# UAVCAN_LIDAR.net
KiCad netlist of a schematic drawn in Altium Designer
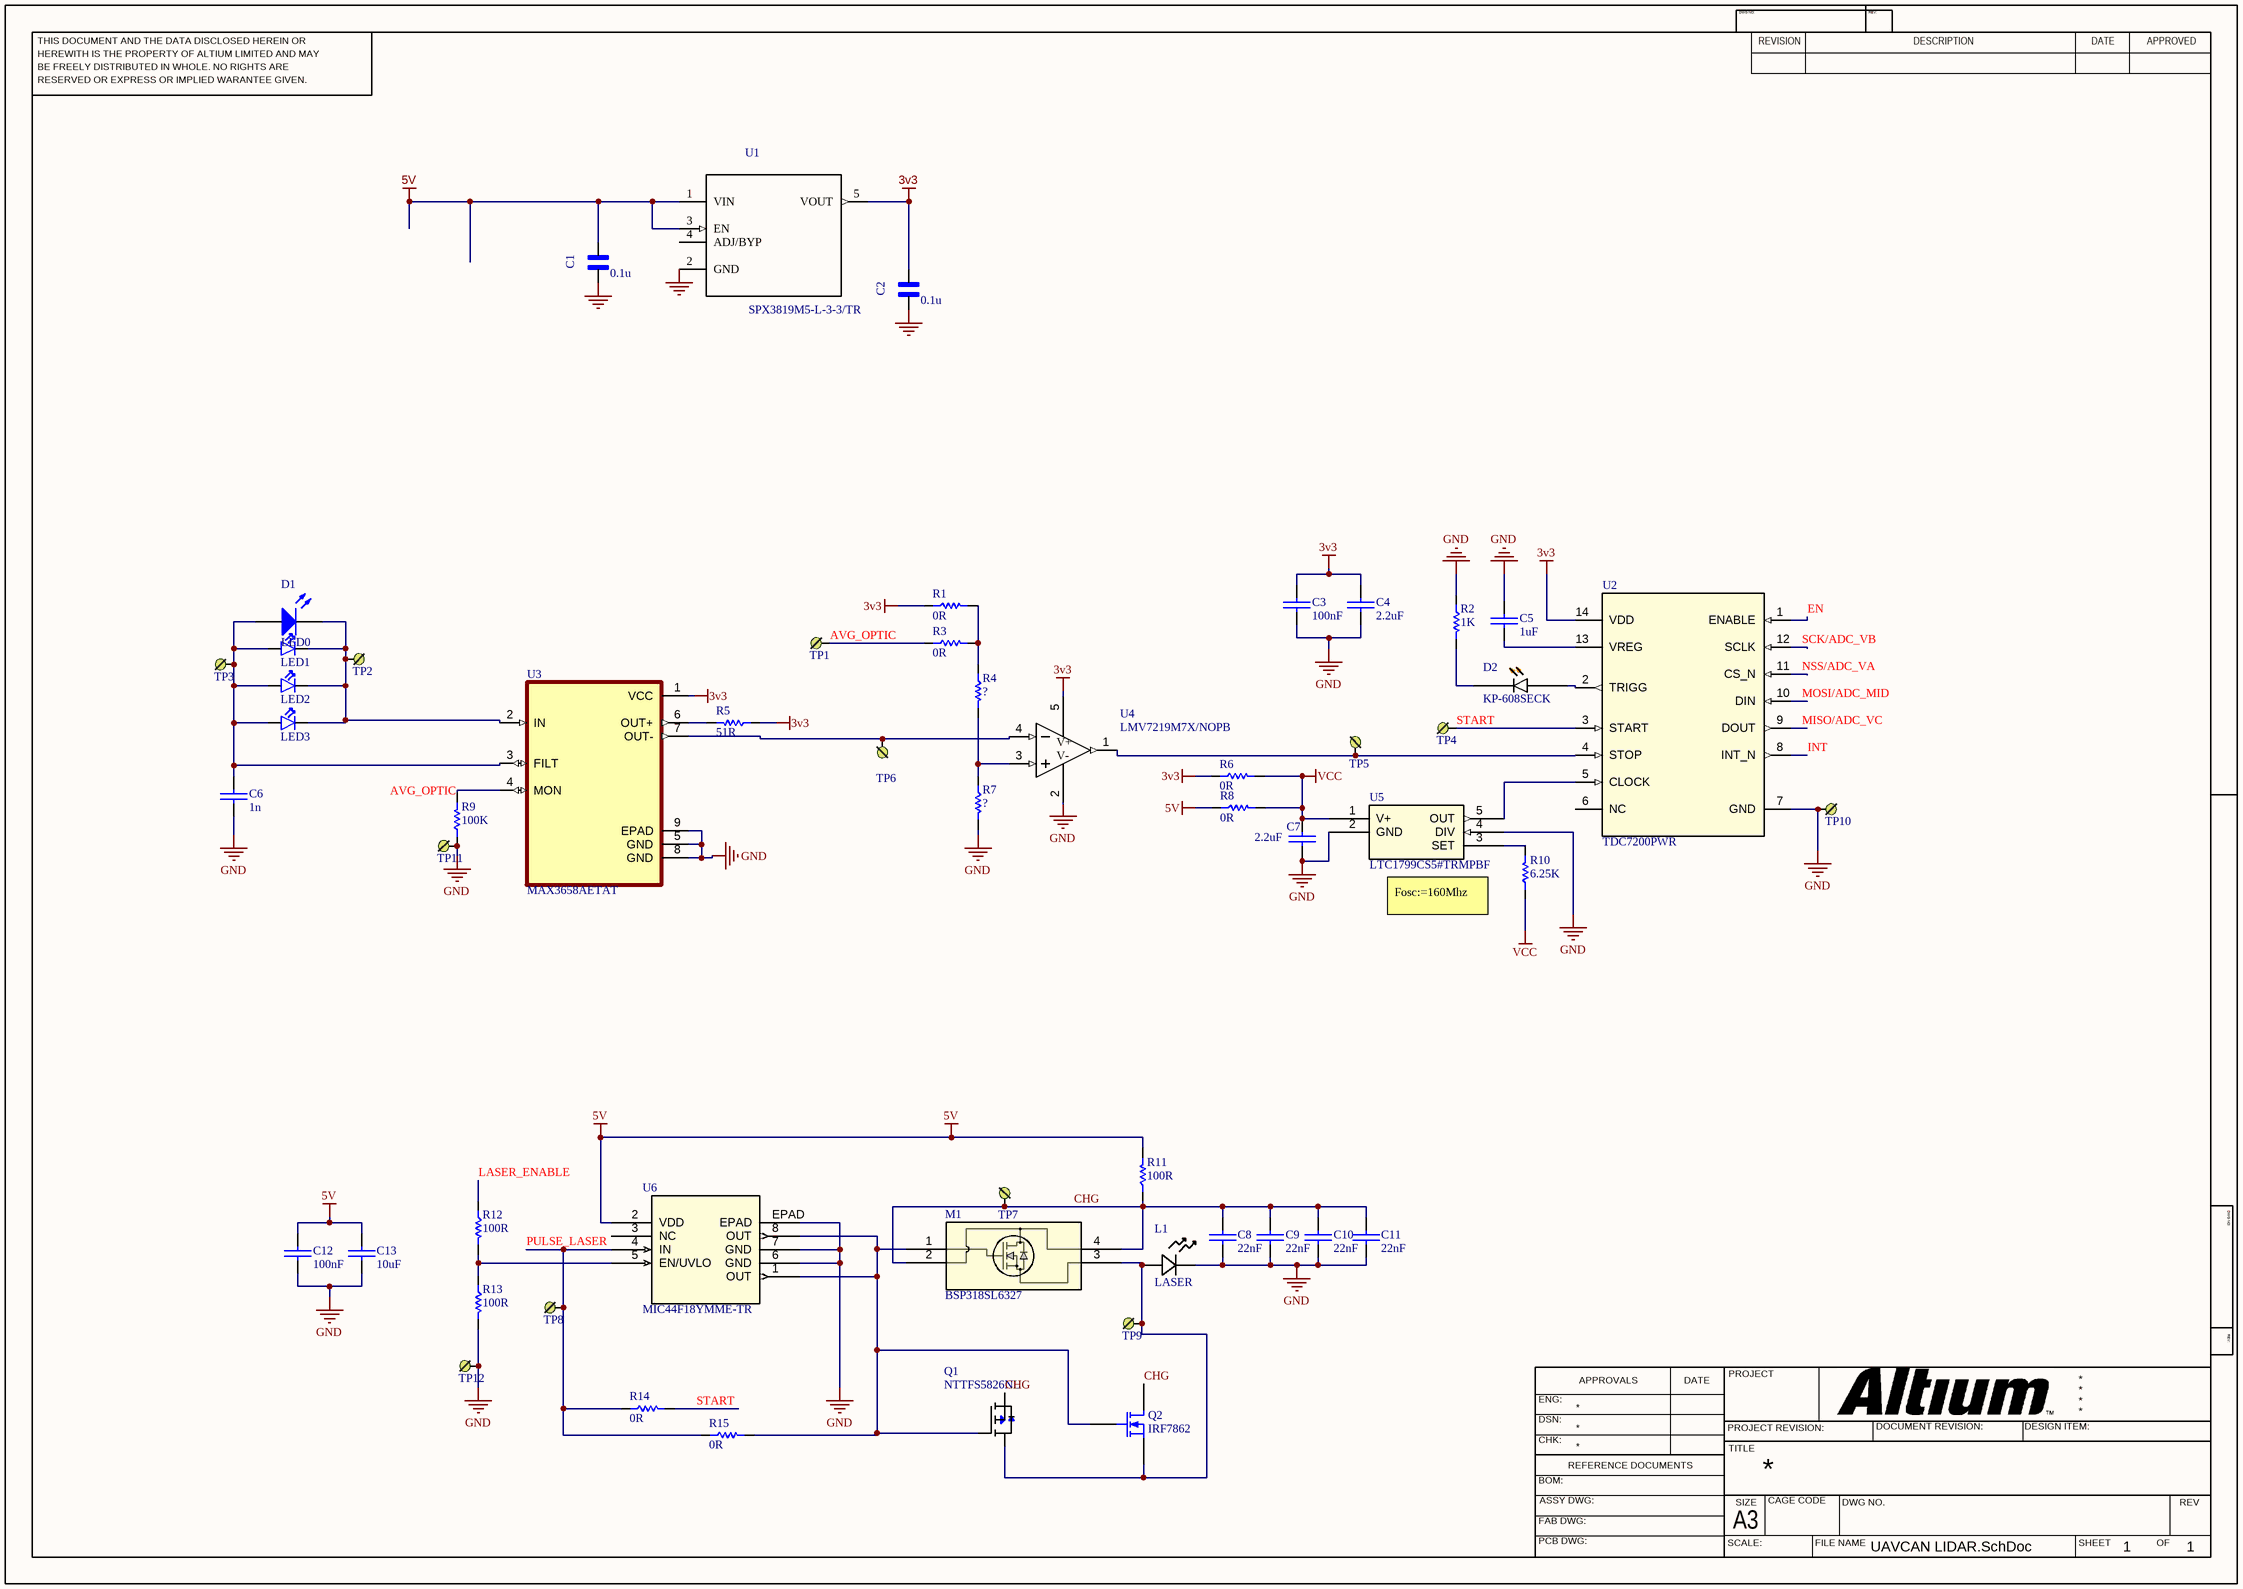
[diagram p0: UAVCAN LIDAR.SchDoc]

(export (version "E")
  (design (tool "Eeschema 10.0.6"))
  (components
    (comp (ref "C1")
      (value "0.1u")
      (footprint "*CAPC1608X90")
      (description "Cap Thin Film 0.1uf 50v 0603")
      (fields (field (name "MF") "AVX") (field (name "MP") "GX035C104MAT2-500"))
      (libsource (lib "lib") (part "GX035C104MAT2-500"))
    )
    (comp (ref "C2")
      (value "0.1u")
      (footprint "*CAPC1608X90")
      (description "Cap Thin Film 0.1uf 50v 0603")
      (fields (field (name "MF") "AVX") (field (name "MP") "GX035C104MAT2-500"))
      (libsource (lib "lib") (part "GX035C104MAT2-500"))
    )
    (comp (ref "C3")
      (value "100nF")
      (footprint "SMD_CAP_0603")
      (description "Bipolar Capacitor")
      (fields (field (name "VOLTAGE") "100V") (field (name "DESIGNER") "Saeid Jorablo"))
      (libsource (lib "R2T Team Library") (part "Cap-Bipolar"))
    )
    (comp (ref "C4")
      (value "2.2uF")
      (footprint "SMD_CAP_0603")
      (description "Bipolar Capacitor")
      (fields (field (name "VOLTAGE") "100V") (field (name "DESIGNER") "Saeid Jorablo"))
      (libsource (lib "R2T Team Library") (part "Cap-Bipolar"))
    )
    (comp (ref "C5")
      (value "1uF")
      (footprint "SMD_CAP_0603")
      (description "Bipolar Capacitor")
      (fields (field (name "VOLTAGE") "100V") (field (name "DESIGNER") "Saeid Jorablo"))
      (libsource (lib "R2T Team Library") (part "Cap-Bipolar"))
    )
    (comp (ref "C6")
      (value "1n")
      (footprint "SMD_CAP_0603")
      (description "Bipolar Capacitor")
      (fields (field (name "VOLTAGE") "100V") (field (name "DESIGNER") "Saeid Jorablo"))
      (libsource (lib "R2T Team Library") (part "Cap-Bipolar"))
    )
    (comp (ref "C7")
      (value "2.2uF")
      (footprint "SMD_CAP_0603")
      (description "Bipolar Capacitor")
      (fields (field (name "VOLTAGE") "100V") (field (name "DESIGNER") "Saeid Jorablo"))
      (libsource (lib "R2T Team Library") (part "Cap-Bipolar"))
    )
    (comp (ref "C8")
      (value "22nF")
      (footprint "SMD_CAP_0603")
      (description "Bipolar Capacitor")
      (fields (field (name "VOLTAGE") "100V") (field (name "DESIGNER") "Saeid Jorablo"))
      (libsource (lib "R2T Team Library") (part "Cap-Bipolar"))
    )
    (comp (ref "C9")
      (value "22nF")
      (footprint "SMD_CAP_0603")
      (description "Bipolar Capacitor")
      (fields (field (name "VOLTAGE") "100V") (field (name "DESIGNER") "Saeid Jorablo"))
      (libsource (lib "R2T Team Library") (part "Cap-Bipolar"))
    )
    (comp (ref "C10")
      (value "22nF")
      (footprint "SMD_CAP_0603")
      (description "Bipolar Capacitor")
      (fields (field (name "VOLTAGE") "100V") (field (name "DESIGNER") "Saeid Jorablo"))
      (libsource (lib "R2T Team Library") (part "Cap-Bipolar"))
    )
    (comp (ref "C11")
      (value "22nF")
      (footprint "SMD_CAP_0603")
      (description "Bipolar Capacitor")
      (fields (field (name "VOLTAGE") "100V") (field (name "DESIGNER") "Saeid Jorablo"))
      (libsource (lib "R2T Team Library") (part "Cap-Bipolar"))
    )
    (comp (ref "C12")
      (value "100nF")
      (footprint "SMD_CAP_0603")
      (description "Bipolar Capacitor")
      (fields (field (name "VOLTAGE") "100V") (field (name "DESIGNER") "Saeid Jorablo"))
      (libsource (lib "R2T Team Library") (part "Cap-Bipolar"))
    )
    (comp (ref "C13")
      (value "10uF")
      (footprint "SMD_CAP_0603")
      (description "Bipolar Capacitor")
      (fields (field (name "VOLTAGE") "100V") (field (name "DESIGNER") "Saeid Jorablo"))
      (libsource (lib "R2T Team Library") (part "Cap-Bipolar"))
    )
    (comp (ref "D1")
      (value "LED0")
      (footprint "LED-0")
      (description "Typical INFRARED GaAs LED")
      (fields (field (name "PUBLISHER") "Altium Limited"))
      (libsource (lib "Miscellaneous Devices") (part "LED0"))
    )
    (comp (ref "D2")
      (value "KP-608SECK")
      (footprint "*LEDM1608X80_LTE-C1906R-14(Primary)")
      (description "Orange 605nm LED Indication - Discrete 2.2V 0603 (1608 Metric)")
      (fields (field (name "MP") "SML-D12D1WT86 or LTST-C194KFKT"))
      (libsource (lib "lib") (part "0603-LED-ORANGE"))
    )
    (comp (ref "L1")
      (value "LASER")
      (footprint "SPL-PL90")
      (description "5mm Laser beam transmitter")
      (fields (field (name "DESIGNER") "EhsanShaghaei"))
      (libsource (lib "lib") (part "SPL-PL90"))
    )
    (comp (ref "LED1")
      (value "LED")
      (footprint "LED1206")
      (fields (field (name "DESIGNER :") "Razi Research Team Of Mashhad - Hamed Jafarzadeh"))
      (libsource (lib "R2T Team Library") (part "LED"))
    )
    (comp (ref "LED2")
      (value "LED")
      (footprint "LED0805")
      (fields (field (name "DESIGNER :") "Razi Research Team Of Mashhad - Hamed Jafarzadeh"))
      (libsource (lib "R2T Team Library") (part "LED"))
    )
    (comp (ref "LED3")
      (value "LED")
      (footprint "LED0603")
      (fields (field (name "DESIGNER :") "Razi Research Team Of Mashhad - Hamed Jafarzadeh"))
      (libsource (lib "R2T Team Library") (part "LED"))
    )
    (comp (ref "M1")
      (value "BSP318SL6327")
      (footprint "PG-SOT223-4_INF-L")
      (description "No Description Available")
      (fields
        (field (name "COPYRIGHT") "Copyright (C) 2018 Accelerated Designs. All rights reserved")
        (field (name "DESIGNER") "EhsanShaghaei")
      )
      (libsource (lib "lib") (part "BSP318SL6327"))
    )
    (comp (ref "Q1")
      (value "NTTFS5826NL")
      (footprint "*TRANS_NVTFS015N04CTAG")
      (description "NTTFS5826NLTAG, MOSFET N-CHANNEL 60V 20A 24MOHM WDFN8")
      (libsource (lib "lib") (part "NTTFS5826NL"))
    )
    (comp (ref "Q2")
      (value "IRF7862")
      (footprint "*SO-08")
      (description "N-Channel MOSFET")
      (fields (field (name "PUBLISHER") "Altium Limited"))
      (libsource (lib "lib") (part "IRF7862"))
    )
    (comp (ref "R1")
      (value "0R")
      (footprint "RES 0603 (1608X06L)")
      (description "Resistor")
      (fields (field (name "TOLERANCE") "5%") (field (name "POWER") "1/8 W"))
      (libsource (lib "R2T Team Library") (part "Resistor"))
    )
    (comp (ref "R2")
      (value "1K")
      (footprint "RES 0603 (1608X06L)")
      (description "Resistor")
      (fields (field (name "TOLERANCE") "5%") (field (name "POWER") "1/8 W"))
      (libsource (lib "R2T Team Library") (part "Resistor"))
    )
    (comp (ref "R3")
      (value "0R")
      (footprint "RES 0603 (1608X06L)")
      (description "Resistor")
      (fields (field (name "TOLERANCE") "5%") (field (name "POWER") "1/8 W"))
      (libsource (lib "R2T Team Library") (part "Resistor"))
    )
    (comp (ref "R4")
      (value "?")
      (footprint "RES 0603 (1608X06L)")
      (description "Resistor")
      (fields (field (name "TOLERANCE") "5%") (field (name "POWER") "1/8 W"))
      (libsource (lib "R2T Team Library") (part "Resistor"))
    )
    (comp (ref "R5")
      (value "51R")
      (footprint "RES 0603 (1608X06L)")
      (description "Resistor")
      (fields (field (name "TOLERANCE") "5%") (field (name "POWER") "1/8 W"))
      (libsource (lib "R2T Team Library") (part "Resistor"))
    )
    (comp (ref "R6")
      (value "0R")
      (footprint "RES 0603 (1608X06L)")
      (description "Resistor")
      (fields (field (name "TOLERANCE") "5%") (field (name "POWER") "1/8 W"))
      (libsource (lib "R2T Team Library") (part "Resistor"))
    )
    (comp (ref "R7")
      (value "?")
      (footprint "RES 0603 (1608X06L)")
      (description "Resistor")
      (fields (field (name "TOLERANCE") "5%") (field (name "POWER") "1/8 W"))
      (libsource (lib "R2T Team Library") (part "Resistor"))
    )
    (comp (ref "R8")
      (value "0R")
      (footprint "RES 0603 (1608X06L)")
      (description "Resistor")
      (fields (field (name "TOLERANCE") "5%") (field (name "POWER") "1/8 W"))
      (libsource (lib "R2T Team Library") (part "Resistor"))
    )
    (comp (ref "R9")
      (value "100K")
      (footprint "RES 0603 (1608X06L)")
      (description "Resistor")
      (fields (field (name "TOLERANCE") "5%") (field (name "POWER") "1/8 W"))
      (libsource (lib "R2T Team Library") (part "Resistor"))
    )
    (comp (ref "R10")
      (value "6.25K")
      (footprint "RES 0603 (1608X06L)")
      (description "Resistor")
      (fields (field (name "TOLERANCE") "5%") (field (name "POWER") "1/8 W"))
      (libsource (lib "R2T Team Library") (part "Resistor"))
    )
    (comp (ref "R11")
      (value "100R")
      (footprint "RES 1210 (3226X07L)")
      (description "Resistor")
      (fields (field (name "TOLERANCE") "5%") (field (name "POWER") "1/8 W"))
      (libsource (lib "R2T Team Library") (part "Resistor"))
    )
    (comp (ref "R12")
      (value "100R")
      (footprint "RES 0603 (1608X06L)")
      (description "Resistor")
      (fields (field (name "TOLERANCE") "5%") (field (name "POWER") "1/8 W"))
      (libsource (lib "R2T Team Library") (part "Resistor"))
    )
    (comp (ref "R13")
      (value "100R")
      (footprint "RES 0603 (1608X06L)")
      (description "Resistor")
      (fields (field (name "TOLERANCE") "5%") (field (name "POWER") "1/8 W"))
      (libsource (lib "R2T Team Library") (part "Resistor"))
    )
    (comp (ref "R14")
      (value "0R")
      (footprint "RES 0603 (1608X06L)")
      (description "Resistor")
      (fields (field (name "TOLERANCE") "5%") (field (name "POWER") "1/8 W"))
      (libsource (lib "R2T Team Library") (part "Resistor"))
    )
    (comp (ref "R15")
      (value "0R")
      (footprint "RES 0603 (1608X06L)")
      (description "Resistor")
      (fields (field (name "TOLERANCE") "5%") (field (name "POWER") "1/8 W"))
      (libsource (lib "R2T Team Library") (part "Resistor"))
    )
    (comp (ref "TP1") (value "Test Point") (footprint "PAD1") (libsource (lib "lib") (part "PLUG")))
    (comp (ref "TP2") (value "Test Point") (footprint "PAD1") (libsource (lib "lib") (part "PLUG")))
    (comp (ref "TP3") (value "Test Point") (footprint "PAD1") (libsource (lib "lib") (part "PLUG")))
    (comp (ref "TP4") (value "Test Point") (footprint "PAD1") (libsource (lib "lib") (part "PLUG")))
    (comp (ref "TP5") (value "Test Point") (footprint "PAD1") (libsource (lib "lib") (part "PLUG")))
    (comp (ref "TP6") (value "Test Point") (footprint "PAD1") (libsource (lib "lib") (part "PLUG")))
    (comp (ref "TP7") (value "Test Point") (footprint "PAD1") (libsource (lib "lib") (part "PLUG")))
    (comp (ref "TP8") (value "Test Point") (footprint "PAD1") (libsource (lib "lib") (part "PLUG")))
    (comp (ref "TP9") (value "Test Point") (footprint "PAD1") (libsource (lib "lib") (part "PLUG")))
    (comp (ref "TP10") (value "Test Point") (footprint "PAD1") (libsource (lib "lib") (part "PLUG")))
    (comp (ref "TP11") (value "Test Point") (footprint "PAD1") (libsource (lib "lib") (part "PLUG")))
    (comp (ref "TP12") (value "Test Point") (footprint "PAD1") (libsource (lib "lib") (part "PLUG")))
    (comp (ref "U1")
      (value "SPX3819M5-L-3-3/TR")
      (footprint "*SOT95P280X145-5N")
      (description "Low Dropout Voltage Regulator, Adjustable 0.5A, В±1%, 2.5 to 16 Vin, 5-Pin SOT-23")
      (fields (field (name "MF") "MaxLinear, Inc."))
      (libsource (lib "DC_DC") (part "SPX3819M5-L"))
    )
    (comp (ref "U2")
      (value "TDC7200PWR")
      (footprint "PW0014A_L")
      (fields (field (name "DESIGNER") "Ehsan Shaghaei"))
      (libsource (lib "lib") (part "TDC7200PWR"))
    )
    (comp (ref "U3")
      (value "MAX3658AETAT")
      (footprint "SON65P300X300X80-9N")
      (fields (field (name "MF") "{'manufacturer': u'Maxim Integrated'}"))
      (libsource (lib "SnapEDA_Library") (part "MAX3658AETAT"))
    )
    (comp (ref "U4")
      (value "LMV7219M7X/NOPB")
      (footprint "SOT-5_S_LIT")
      (fields
        (field (name "PARTNUMBER") "LMV7219M7")
        (field (name "MANUFACTURER") "NationalSemiconductor")
        (field (name "COPYRIGHT") "Copyright (C) 2018 Accelerated Designs. All rights reserved")
        (field (name "PUBLISHER") "NationalSemiconductor")
        (field (name "DESIGNER") "EhsanShaghaei")
      )
      (libsource (lib "lib") (part "LMV7219M7X/NOPB"))
    )
    (comp (ref "U5")
      (value "LTC1799CS5#TRMPBF")
      (footprint "SOT-5_S_LIT")
      (fields (field (name "COPYRIGHT") "Copyright (C) 2018 Accelerated Designs. All rights reserved"))
      (libsource (lib "lib") (part "LTC1799CS5"))
    )
    (comp (ref "U6")
      (value "MIC44F18YMME-TR")
      (footprint "SOP65P490X104-9N")
      (description "No Description Available")
      (fields
        (field (name "COPYRIGHT") "Copyright (C) 2018 Accelerated Designs. All rights reserved")
        (field (name "DESIGNER") "Ehsan Shaghaei")
      )
      (libsource (lib "lib") (part "MIC44F18YMME-TR"))
    )
  )
  (nets
    (net (code "1") (name "/AVG_OPTIC") (class "Default")
      (node (ref "R3") (pin "1") (pinfunction "1_1") (pintype "passive"))
      (node (ref "R9") (pin "2") (pinfunction "2_2") (pintype "passive"))
      (node (ref "TP1") (pin "1") (pintype "passive"))
      (node (ref "U3") (pin "4") (pinfunction "MON_4") (pintype "bidirectional"))
    )
    (net (code "2") (name "/CHG") (class "Default")
      (node (ref "C10") (pin "1") (pinfunction "+_1") (pintype "passive"))
      (node (ref "C11") (pin "1") (pinfunction "+_1") (pintype "passive"))
      (node (ref "C8") (pin "1") (pinfunction "+_1") (pintype "passive"))
      (node (ref "C9") (pin "1") (pinfunction "+_1") (pintype "passive"))
      (node (ref "M1") (pin "2") (pinfunction "2_2") (pintype "passive"))
      (node (ref "M1") (pin "4") (pinfunction "4_4") (pintype "passive"))
      (node (ref "Q1") (pin "S") (pinfunction "S_S") (pintype "passive"))
      (node (ref "Q2") (pin "D") (pinfunction "D_D") (pintype "passive"))
      (node (ref "R11") (pin "1") (pinfunction "1_1") (pintype "passive"))
      (node (ref "TP7") (pin "1") (pintype "passive"))
    )
    (net (code "3") (name "/EN") (class "Default")
      (node (ref "U2") (pin "1") (pinfunction "ENABLE_1") (pintype "input"))
    )
    (net (code "4") (name "/INT") (class "Default")
      (node (ref "U2") (pin "8") (pinfunction "INT_N_8") (pintype "output"))
    )
    (net (code "5") (name "/LASER_ENABLE") (class "Default")
      (node (ref "R12") (pin "1") (pinfunction "1_1") (pintype "passive"))
    )
    (net (code "6") (name "/MISO{slash}ADC_VC") (class "Default")
      (node (ref "U2") (pin "9") (pinfunction "DOUT_9") (pintype "output"))
    )
    (net (code "7") (name "/MOSI{slash}ADC_MID") (class "Default")
      (node (ref "U2") (pin "10") (pinfunction "DIN_10") (pintype "input"))
    )
    (net (code "8") (name "/NSS{slash}ADC_VA") (class "Default")
      (node (ref "U2") (pin "11") (pinfunction "CS_N_11") (pintype "input"))
    )
    (net (code "9") (name "/PULSE_LASER") (class "Default")
      (node (ref "R14") (pin "1") (pinfunction "1_1") (pintype "passive"))
      (node (ref "R15") (pin "1") (pinfunction "1_1") (pintype "passive"))
      (node (ref "TP8") (pin "1") (pintype "passive"))
      (node (ref "U6") (pin "4") (pinfunction "IN_4") (pintype "input"))
    )
    (net (code "10") (name "/SCK{slash}ADC_VB") (class "Default")
      (node (ref "U2") (pin "12") (pinfunction "SCLK_12") (pintype "input"))
    )
    (net (code "11") (name "/START") (class "Default")
      (node (ref "R14") (pin "2") (pinfunction "2_2") (pintype "passive"))
      (node (ref "TP4") (pin "1") (pintype "passive"))
      (node (ref "U2") (pin "3") (pinfunction "START_3") (pintype "input"))
    )
    (net (code "12") (name "3v3") (class "Default")
      (node (ref "C2") (pin "1") (pinfunction "1_1") (pintype "passive"))
      (node (ref "C3") (pin "1") (pinfunction "+_1") (pintype "passive"))
      (node (ref "C4") (pin "1") (pinfunction "+_1") (pintype "passive"))
      (node (ref "R1") (pin "1") (pinfunction "1_1") (pintype "passive"))
      (node (ref "R5") (pin "1") (pinfunction "1_1") (pintype "passive"))
      (node (ref "R6") (pin "1") (pinfunction "1_1") (pintype "passive"))
      (node (ref "U1") (pin "5") (pinfunction "VOUT_5") (pintype "output"))
      (node (ref "U2") (pin "14") (pinfunction "VDD_14") (pintype "power_in"))
      (node (ref "U3") (pin "1") (pinfunction "VCC_1") (pintype "power_in"))
      (node (ref "U4") (pin "5") (pinfunction "V+_5") (pintype "power_in"))
    )
    (net (code "13") (name "5V") (class "Default")
      (node (ref "C1") (pin "1") (pinfunction "1_1") (pintype "passive"))
      (node (ref "C12") (pin "1") (pinfunction "+_1") (pintype "passive"))
      (node (ref "C13") (pin "1") (pinfunction "+_1") (pintype "passive"))
      (node (ref "R11") (pin "2") (pinfunction "2_2") (pintype "passive"))
      (node (ref "R8") (pin "1") (pinfunction "1_1") (pintype "passive"))
      (node (ref "U1") (pin "1") (pinfunction "VIN_1") (pintype "power_in"))
      (node (ref "U1") (pin "3") (pinfunction "EN_3") (pintype "input"))
      (node (ref "U6") (pin "2") (pinfunction "VDD_2") (pintype "power_in"))
    )
    (net (code "14") (name "GND") (class "Default")
      (node (ref "C1") (pin "2") (pinfunction "2_2") (pintype "passive"))
      (node (ref "C10") (pin "2") (pinfunction "-_2") (pintype "passive"))
      (node (ref "C11") (pin "2") (pinfunction "-_2") (pintype "passive"))
      (node (ref "C12") (pin "2") (pinfunction "-_2") (pintype "passive"))
      (node (ref "C13") (pin "2") (pinfunction "-_2") (pintype "passive"))
      (node (ref "C2") (pin "2") (pinfunction "2_2") (pintype "passive"))
      (node (ref "C3") (pin "2") (pinfunction "-_2") (pintype "passive"))
      (node (ref "C4") (pin "2") (pinfunction "-_2") (pintype "passive"))
      (node (ref "C5") (pin "1") (pinfunction "+_1") (pintype "passive"))
      (node (ref "C6") (pin "2") (pinfunction "-_2") (pintype "passive"))
      (node (ref "C7") (pin "2") (pinfunction "-_2") (pintype "passive"))
      (node (ref "C8") (pin "2") (pinfunction "-_2") (pintype "passive"))
      (node (ref "C9") (pin "2") (pinfunction "-_2") (pintype "passive"))
      (node (ref "L1") (pin "1") (pinfunction "1_1") (pintype "passive"))
      (node (ref "R13") (pin "2") (pinfunction "2_2") (pintype "passive"))
      (node (ref "R2") (pin "1") (pinfunction "1_1") (pintype "passive"))
      (node (ref "R7") (pin "2") (pinfunction "2_2") (pintype "passive"))
      (node (ref "R9") (pin "1") (pinfunction "1_1") (pintype "passive"))
      (node (ref "TP10") (pin "1") (pintype "passive"))
      (node (ref "TP11") (pin "1") (pintype "passive"))
      (node (ref "TP12") (pin "1") (pintype "passive"))
      (node (ref "U1") (pin "2") (pinfunction "GND_2") (pintype "passive"))
      (node (ref "U2") (pin "7") (pinfunction "GND_7") (pintype "power_in"))
      (node (ref "U3") (pin "5") (pinfunction "GND_5") (pintype "power_in"))
      (node (ref "U3") (pin "8") (pinfunction "GND_8") (pintype "power_in"))
      (node (ref "U3") (pin "9") (pinfunction "EPAD_9") (pintype "power_in"))
      (node (ref "U4") (pin "2") (pinfunction "V-_2") (pintype "power_in"))
      (node (ref "U5") (pin "2") (pinfunction "GND_2") (pintype "power_in"))
      (node (ref "U5") (pin "4") (pinfunction "DIV_4") (pintype "input"))
      (node (ref "U6") (pin "6") (pinfunction "GND_6") (pintype "power_in"))
      (node (ref "U6") (pin "7") (pinfunction "GND_7") (pintype "power_in"))
      (node (ref "U6") (pin "EPAD") (pinfunction "EPAD_EPAD") (pintype "passive"))
    )
    (net (code "15") (name "Net-(C5--)") (class "Default")
      (node (ref "C5") (pin "2") (pinfunction "-_2") (pintype "passive"))
      (node (ref "U2") (pin "13") (pinfunction "VREG_13") (pintype "power_in"))
    )
    (net (code "16") (name "Net-(C6-+)") (class "Default")
      (node (ref "C6") (pin "1") (pinfunction "+_1") (pintype "passive"))
      (node (ref "D1") (pin "1") (pinfunction "A_1") (pintype "passive"))
      (node (ref "LED1") (pin "1") (pinfunction "A_1") (pintype "passive"))
      (node (ref "LED2") (pin "1") (pinfunction "A_1") (pintype "passive"))
      (node (ref "LED3") (pin "1") (pinfunction "A_1") (pintype "passive"))
      (node (ref "TP3") (pin "1") (pintype "passive"))
      (node (ref "U3") (pin "3") (pinfunction "FILT_3") (pintype "bidirectional"))
    )
    (net (code "17") (name "Net-(D1-K)") (class "Default")
      (node (ref "D1") (pin "2") (pinfunction "K_2") (pintype "passive"))
      (node (ref "LED1") (pin "2") (pinfunction "K_2") (pintype "passive"))
      (node (ref "LED2") (pin "2") (pinfunction "K_2") (pintype "passive"))
      (node (ref "LED3") (pin "2") (pinfunction "K_2") (pintype "passive"))
      (node (ref "TP2") (pin "1") (pintype "passive"))
      (node (ref "U3") (pin "2") (pinfunction "IN_2") (pintype "input"))
    )
    (net (code "18") (name "Net-(D2-PadC)") (class "Default")
      (node (ref "D2") (pin "C") (pinfunction "C_C") (pintype "passive"))
      (node (ref "R2") (pin "2") (pinfunction "2_2") (pintype "passive"))
    )
    (net (code "19") (name "Net-(L1-Pad2)") (class "Default")
      (node (ref "L1") (pin "2") (pinfunction "2_2") (pintype "passive"))
      (node (ref "M1") (pin "3") (pinfunction "3_3") (pintype "passive"))
      (node (ref "Q1") (pin "D") (pinfunction "D_D") (pintype "passive"))
      (node (ref "Q2") (pin "S") (pinfunction "S_S") (pintype "passive"))
      (node (ref "TP9") (pin "1") (pintype "passive"))
    )
    (net (code "20") (name "Net-(M1-Pad1)") (class "Default")
      (node (ref "M1") (pin "1") (pinfunction "1_1") (pintype "passive"))
      (node (ref "Q1") (pin "G") (pinfunction "G_G") (pintype "passive"))
      (node (ref "Q2") (pin "G") (pinfunction "G_G") (pintype "passive"))
      (node (ref "R15") (pin "2") (pinfunction "2_2") (pintype "passive"))
      (node (ref "U6") (pin "1") (pinfunction "OUT_1") (pintype "output"))
      (node (ref "U6") (pin "8") (pinfunction "OUT_8") (pintype "output"))
    )
    (net (code "21") (name "Net-(R1-Pad2)") (class "Default")
      (node (ref "R1") (pin "2") (pinfunction "2_2") (pintype "passive"))
      (node (ref "R3") (pin "2") (pinfunction "2_2") (pintype "passive"))
      (node (ref "R4") (pin "1") (pinfunction "1_1") (pintype "passive"))
    )
    (net (code "22") (name "Net-(U2-CLOCK)") (class "Default")
      (node (ref "U2") (pin "5") (pinfunction "CLOCK_5") (pintype "input"))
      (node (ref "U5") (pin "5") (pinfunction "OUT_5") (pintype "output"))
    )
    (net (code "23") (name "Net-(U2-STOP)") (class "Default")
      (node (ref "TP5") (pin "1") (pintype "passive"))
      (node (ref "U2") (pin "4") (pinfunction "STOP_4") (pintype "input"))
      (node (ref "U4") (pin "1") (pinfunction "OUT_1") (pintype "output"))
    )
    (net (code "24") (name "Net-(U2-TRIGG)") (class "Default")
      (node (ref "D2") (pin "A") (pinfunction "A_A") (pintype "passive"))
      (node (ref "U2") (pin "2") (pinfunction "TRIGG_2") (pintype "output"))
    )
    (net (code "25") (name "Net-(U3-OUT+)") (class "Default")
      (node (ref "R5") (pin "2") (pinfunction "2_2") (pintype "passive"))
      (node (ref "U3") (pin "6") (pinfunction "OUT+_6") (pintype "output"))
    )
    (net (code "26") (name "Net-(U3-OUT-)") (class "Default")
      (node (ref "TP6") (pin "1") (pintype "passive"))
      (node (ref "U3") (pin "7") (pinfunction "OUT-_7") (pintype "output"))
      (node (ref "U4") (pin "4") (pinfunction "IN-_4") (pintype "input"))
    )
    (net (code "27") (name "Net-(U4-IN+)") (class "Default")
      (node (ref "R4") (pin "2") (pinfunction "2_2") (pintype "passive"))
      (node (ref "R7") (pin "1") (pinfunction "1_1") (pintype "passive"))
      (node (ref "U4") (pin "3") (pinfunction "IN+_3") (pintype "input"))
    )
    (net (code "28") (name "Net-(U5-SET)") (class "Default")
      (node (ref "R10") (pin "2") (pinfunction "2_2") (pintype "passive"))
      (node (ref "U5") (pin "3") (pinfunction "SET_3") (pintype "passive"))
    )
    (net (code "29") (name "Net-(U6-EN{slash}UVLO)") (class "Default")
      (node (ref "R12") (pin "2") (pinfunction "2_2") (pintype "passive"))
      (node (ref "R13") (pin "1") (pinfunction "1_1") (pintype "passive"))
      (node (ref "U6") (pin "5") (pinfunction "EN/UVLO_5") (pintype "input"))
    )
    (net (code "30") (name "VCC") (class "Default")
      (node (ref "C7") (pin "1") (pinfunction "+_1") (pintype "passive"))
      (node (ref "R10") (pin "1") (pinfunction "1_1") (pintype "passive"))
      (node (ref "R6") (pin "2") (pinfunction "2_2") (pintype "passive"))
      (node (ref "R8") (pin "2") (pinfunction "2_2") (pintype "passive"))
      (node (ref "U5") (pin "1") (pinfunction "V+_1") (pintype "power_in"))
    )
    (net (code "31") (name "unconnected-(U1-ADJ{slash}BYP-Pad4)") (class "Default")
      (node (ref "U1") (pin "4") (pinfunction "ADJ/BYP_4") (pintype "passive"))
    )
    (net (code "32") (name "unconnected-(U2-NC-Pad6)") (class "Default")
      (node (ref "U2") (pin "6") (pinfunction "NC_6") (pintype "passive"))
    )
    (net (code "33") (name "unconnected-(U6-NC-Pad3)") (class "Default")
      (node (ref "U6") (pin "3") (pinfunction "NC_3") (pintype "passive"))
    )
  )
)
